# A4988_motor_drivers.net
KiCad netlist of a schematic drawn in Altium Designer
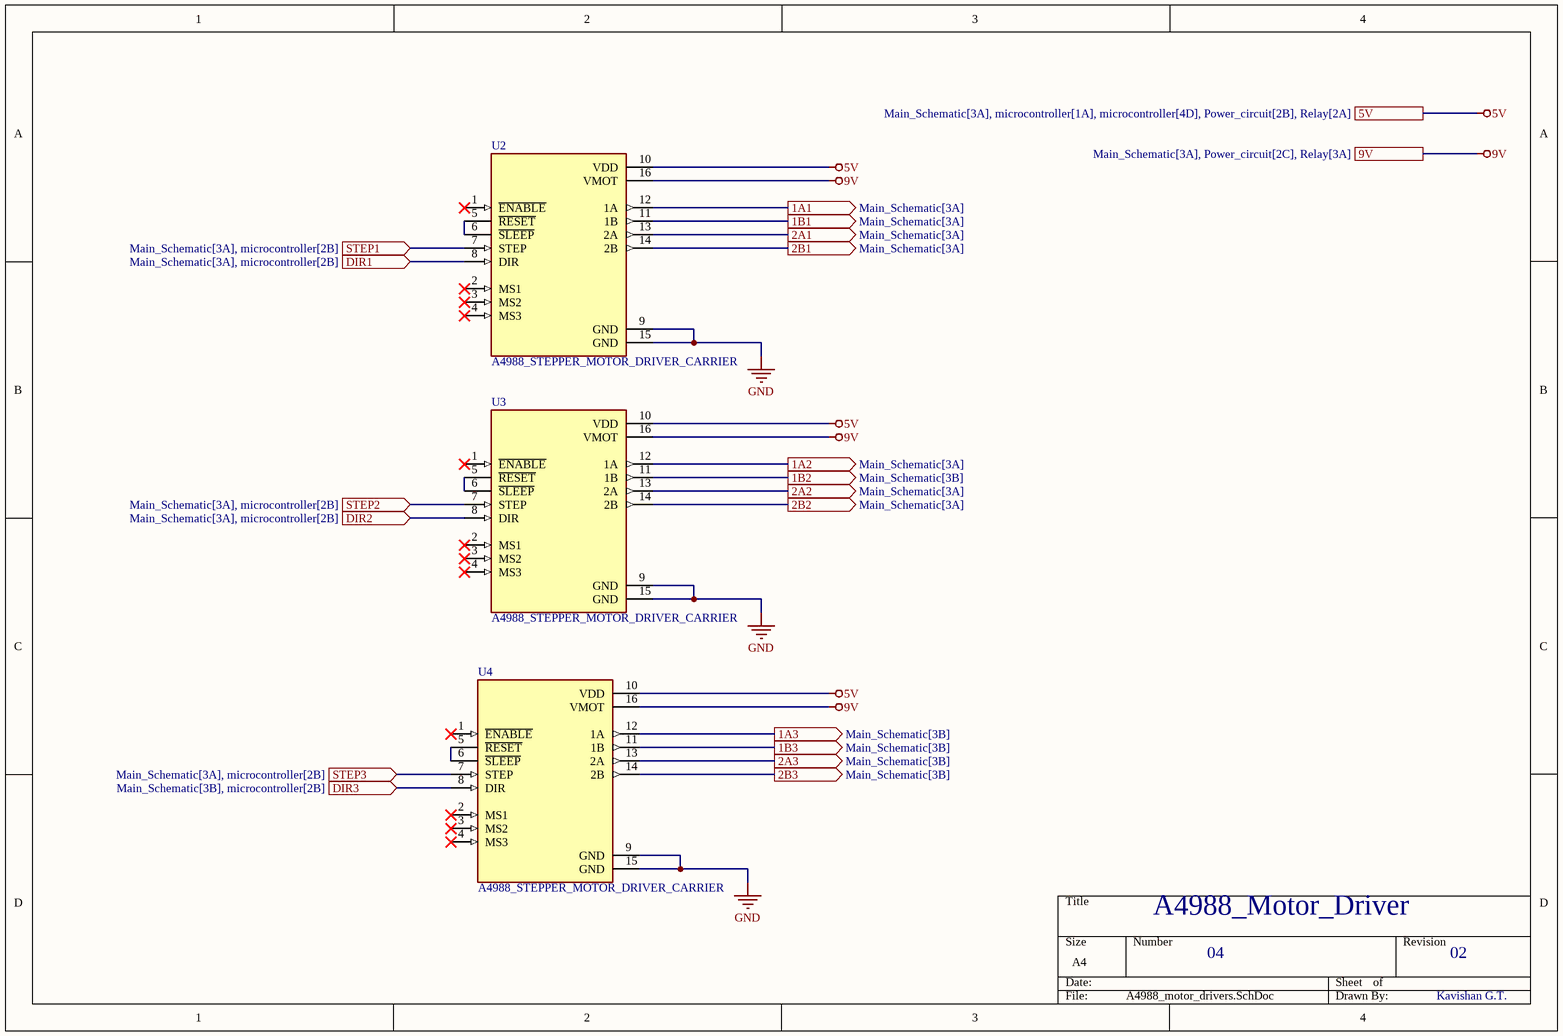
[diagram p0: A4988_motor_drivers.SchDoc]

(export (version "E")
  (design (tool "Eeschema 10.0.6"))
  (components
    (comp (ref "U2")
      (value "A4988_STEPPER_MOTOR_DRIVER_CARRIER")
      (footprint "MODULE_A4988_STEPPER_MOTOR_DRIVER_CARRIER")
      (description "Stepper motor controler; IC: A4988; 1A; Uin mot: 8Ã·35V")
      (libsource (lib "A4988_STEPPER_MOTOR_DRIVER_CARRIER") (part "A4988_STEPPER_MOTOR_DRIVER_CARRIER"))
    )
    (comp (ref "U3")
      (value "A4988_STEPPER_MOTOR_DRIVER_CARRIER")
      (footprint "MODULE_A4988_STEPPER_MOTOR_DRIVER_CARRIER")
      (description "Stepper motor controler; IC: A4988; 1A; Uin mot: 8Ã·35V")
      (libsource (lib "A4988_STEPPER_MOTOR_DRIVER_CARRIER") (part "A4988_STEPPER_MOTOR_DRIVER_CARRIER"))
    )
    (comp (ref "U4")
      (value "A4988_STEPPER_MOTOR_DRIVER_CARRIER")
      (footprint "MODULE_A4988_STEPPER_MOTOR_DRIVER_CARRIER")
      (description "Stepper motor controler; IC: A4988; 1A; Uin mot: 8Ã·35V")
      (libsource (lib "A4988_STEPPER_MOTOR_DRIVER_CARRIER") (part "A4988_STEPPER_MOTOR_DRIVER_CARRIER"))
    )
  )
  (nets
    (net (code "1") (name "/1A1") (class "Default")
      (node (ref "U2") (pin "12") (pinfunction "1A_12") (pintype "output"))
    )
    (net (code "2") (name "/1A2") (class "Default")
      (node (ref "U3") (pin "12") (pinfunction "1A_12") (pintype "output"))
    )
    (net (code "3") (name "/1A3") (class "Default")
      (node (ref "U4") (pin "12") (pinfunction "1A_12") (pintype "output"))
    )
    (net (code "4") (name "/1B1") (class "Default")
      (node (ref "U2") (pin "11") (pinfunction "1B_11") (pintype "output"))
    )
    (net (code "5") (name "/1B2") (class "Default")
      (node (ref "U3") (pin "11") (pinfunction "1B_11") (pintype "output"))
    )
    (net (code "6") (name "/1B3") (class "Default")
      (node (ref "U4") (pin "11") (pinfunction "1B_11") (pintype "output"))
    )
    (net (code "7") (name "/2A1") (class "Default")
      (node (ref "U2") (pin "13") (pinfunction "2A_13") (pintype "output"))
    )
    (net (code "8") (name "/2A2") (class "Default")
      (node (ref "U3") (pin "13") (pinfunction "2A_13") (pintype "output"))
    )
    (net (code "9") (name "/2A3") (class "Default")
      (node (ref "U4") (pin "13") (pinfunction "2A_13") (pintype "output"))
    )
    (net (code "10") (name "/2B1") (class "Default")
      (node (ref "U2") (pin "14") (pinfunction "2B_14") (pintype "output"))
    )
    (net (code "11") (name "/2B2") (class "Default")
      (node (ref "U3") (pin "14") (pinfunction "2B_14") (pintype "output"))
    )
    (net (code "12") (name "/2B3") (class "Default")
      (node (ref "U4") (pin "14") (pinfunction "2B_14") (pintype "output"))
    )
    (net (code "13") (name "/DIR1") (class "Default")
      (node (ref "U2") (pin "8") (pinfunction "DIR_8") (pintype "input"))
    )
    (net (code "14") (name "/DIR2") (class "Default")
      (node (ref "U3") (pin "8") (pinfunction "DIR_8") (pintype "input"))
    )
    (net (code "15") (name "/DIR3") (class "Default")
      (node (ref "U4") (pin "8") (pinfunction "DIR_8") (pintype "input"))
    )
    (net (code "16") (name "/STEP1") (class "Default")
      (node (ref "U2") (pin "7") (pinfunction "STEP_7") (pintype "input"))
    )
    (net (code "17") (name "/STEP2") (class "Default")
      (node (ref "U3") (pin "7") (pinfunction "STEP_7") (pintype "input"))
    )
    (net (code "18") (name "/STEP3") (class "Default")
      (node (ref "U4") (pin "7") (pinfunction "STEP_7") (pintype "input"))
    )
    (net (code "19") (name "5V") (class "Default")
      (node (ref "U2") (pin "10") (pinfunction "VDD_10") (pintype "power_in"))
      (node (ref "U3") (pin "10") (pinfunction "VDD_10") (pintype "power_in"))
      (node (ref "U4") (pin "10") (pinfunction "VDD_10") (pintype "power_in"))
    )
    (net (code "20") (name "9V") (class "Default")
      (node (ref "U2") (pin "16") (pinfunction "VMOT_16") (pintype "power_in"))
      (node (ref "U3") (pin "16") (pinfunction "VMOT_16") (pintype "power_in"))
      (node (ref "U4") (pin "16") (pinfunction "VMOT_16") (pintype "power_in"))
    )
    (net (code "21") (name "GND") (class "Default")
      (node (ref "U2") (pin "15") (pinfunction "GND_15") (pintype "power_in"))
      (node (ref "U2") (pin "9") (pinfunction "GND_9") (pintype "power_in"))
      (node (ref "U3") (pin "15") (pinfunction "GND_15") (pintype "power_in"))
      (node (ref "U3") (pin "9") (pinfunction "GND_9") (pintype "power_in"))
      (node (ref "U4") (pin "15") (pinfunction "GND_15") (pintype "power_in"))
      (node (ref "U4") (pin "9") (pinfunction "GND_9") (pintype "power_in"))
    )
    (net (code "22") (name "Net-(U2-~{RESET})") (class "Default")
      (node (ref "U2") (pin "5") (pinfunction "~{RESET}_5") (pintype "open_collector"))
      (node (ref "U2") (pin "6") (pinfunction "~{SLEEP}_6") (pintype "open_collector"))
    )
    (net (code "23") (name "Net-(U3-~{RESET})") (class "Default")
      (node (ref "U3") (pin "5") (pinfunction "~{RESET}_5") (pintype "open_collector"))
      (node (ref "U3") (pin "6") (pinfunction "~{SLEEP}_6") (pintype "open_collector"))
    )
    (net (code "24") (name "Net-(U4-~{RESET})") (class "Default")
      (node (ref "U4") (pin "5") (pinfunction "~{RESET}_5") (pintype "open_collector"))
      (node (ref "U4") (pin "6") (pinfunction "~{SLEEP}_6") (pintype "open_collector"))
    )
    (net (code "25") (name "unconnected-(U2-MS1-Pad2)") (class "Default")
      (node (ref "U2") (pin "2") (pinfunction "MS1_2") (pintype "input+no_connect"))
    )
    (net (code "26") (name "unconnected-(U2-MS2-Pad3)") (class "Default")
      (node (ref "U2") (pin "3") (pinfunction "MS2_3") (pintype "input+no_connect"))
    )
    (net (code "27") (name "unconnected-(U2-MS3-Pad4)") (class "Default")
      (node (ref "U2") (pin "4") (pinfunction "MS3_4") (pintype "input+no_connect"))
    )
    (net (code "28") (name "unconnected-(U2-~{ENABLE}-Pad1)") (class "Default")
      (node (ref "U2") (pin "1") (pinfunction "~{ENABLE}_1") (pintype "input+no_connect"))
    )
    (net (code "29") (name "unconnected-(U3-MS1-Pad2)") (class "Default")
      (node (ref "U3") (pin "2") (pinfunction "MS1_2") (pintype "input+no_connect"))
    )
    (net (code "30") (name "unconnected-(U3-MS2-Pad3)") (class "Default")
      (node (ref "U3") (pin "3") (pinfunction "MS2_3") (pintype "input+no_connect"))
    )
    (net (code "31") (name "unconnected-(U3-MS3-Pad4)") (class "Default")
      (node (ref "U3") (pin "4") (pinfunction "MS3_4") (pintype "input+no_connect"))
    )
    (net (code "32") (name "unconnected-(U3-~{ENABLE}-Pad1)") (class "Default")
      (node (ref "U3") (pin "1") (pinfunction "~{ENABLE}_1") (pintype "input+no_connect"))
    )
    (net (code "33") (name "unconnected-(U4-MS1-Pad2)") (class "Default")
      (node (ref "U4") (pin "2") (pinfunction "MS1_2") (pintype "input+no_connect"))
    )
    (net (code "34") (name "unconnected-(U4-MS2-Pad3)") (class "Default")
      (node (ref "U4") (pin "3") (pinfunction "MS2_3") (pintype "input+no_connect"))
    )
    (net (code "35") (name "unconnected-(U4-MS3-Pad4)") (class "Default")
      (node (ref "U4") (pin "4") (pinfunction "MS3_4") (pintype "input+no_connect"))
    )
    (net (code "36") (name "unconnected-(U4-~{ENABLE}-Pad1)") (class "Default")
      (node (ref "U4") (pin "1") (pinfunction "~{ENABLE}_1") (pintype "input+no_connect"))
    )
  )
)
